# StairLights.net
KiCad netlist of a schematic drawn in EAGLE
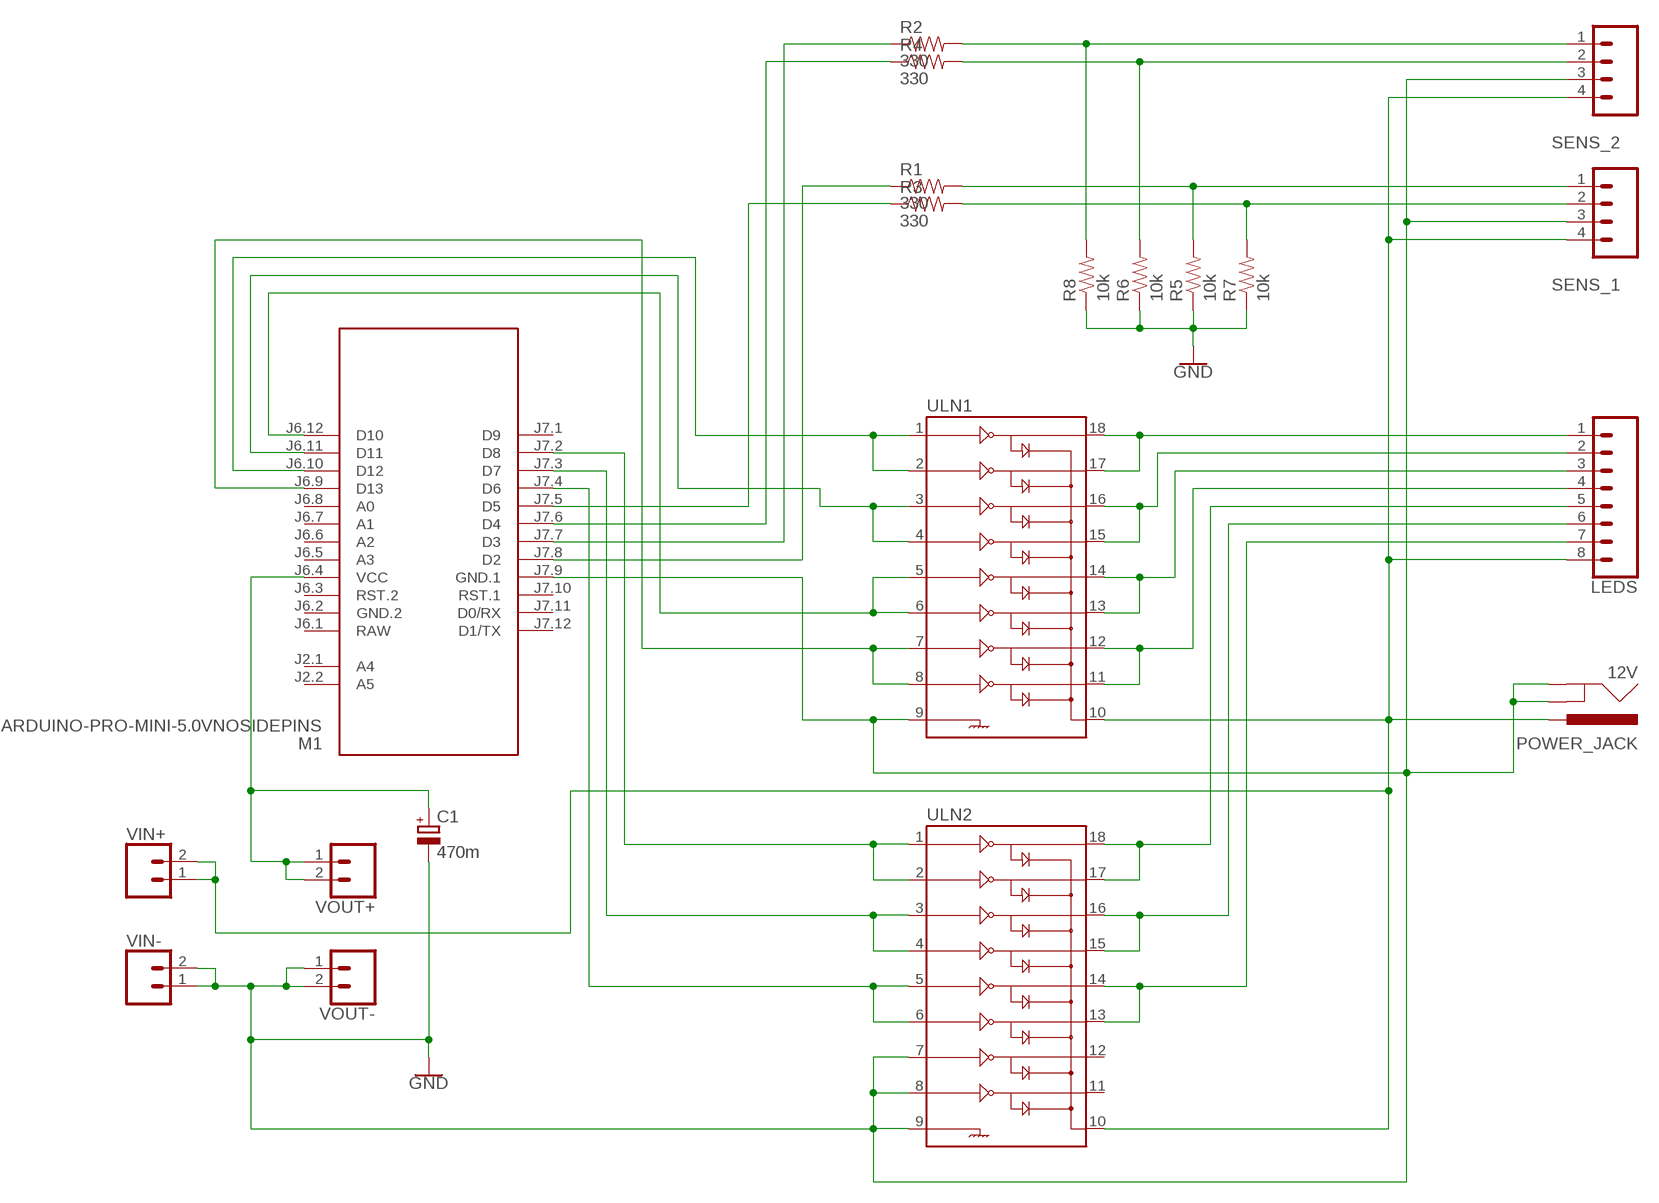
[diagram p0: schematic, sheet 1]

(export (version "E")
  (design (tool "Eeschema 10.0.6"))
  (components
    (comp (ref "12V")
      (value "POWER_JACK")
      (footprint "eagle-import:POWER_JACK_PTH")
      (libsource (lib "eagle-import") (part "POWER_JACK"))
    )
    (comp (ref "C1")
      (value "470m")
      (footprint "eagle-import:E5-5")
      (libsource (lib "eagle-import") (part "CPOL-EUE5-5"))
    )
    (comp (ref "LEDS")
      (value "CONN_08LONGPADS")
      (footprint "eagle-import:1X08_LONGPADS")
      (libsource (lib "eagle-import") (part "CONN_08LONGPADS"))
    )
    (comp (ref "M1")
      (value "ARDUINO-PRO-MINI-5.0VNOSIDEPINS")
      (footprint "eagle-import:ARDUINO-PRO-MINI")
      (libsource (lib "eagle-import") (part "ARDUINO-PRO-MINI-NOSIDEPINS5.0V"))
    )
    (comp (ref "R1")
      (value "330")
      (footprint "eagle-import:AXIAL-0.3")
      (libsource (lib "eagle-import") (part "330OHM-HORIZ-1/10W-5%"))
    )
    (comp (ref "R2")
      (value "330")
      (footprint "eagle-import:AXIAL-0.3")
      (libsource (lib "eagle-import") (part "330OHM-HORIZ-1/10W-5%"))
    )
    (comp (ref "R3")
      (value "330")
      (footprint "eagle-import:AXIAL-0.3")
      (libsource (lib "eagle-import") (part "330OHM-HORIZ-1/10W-5%"))
    )
    (comp (ref "R4")
      (value "330")
      (footprint "eagle-import:AXIAL-0.3")
      (libsource (lib "eagle-import") (part "330OHM-HORIZ-1/10W-5%"))
    )
    (comp (ref "R5")
      (value "10k")
      (footprint "eagle-import:AXIAL-0.3")
      (libsource (lib "eagle-import") (part "330OHM-HORIZ-1/10W-5%"))
    )
    (comp (ref "R6")
      (value "10k")
      (footprint "eagle-import:AXIAL-0.3")
      (libsource (lib "eagle-import") (part "330OHM-HORIZ-1/10W-5%"))
    )
    (comp (ref "R7")
      (value "10k")
      (footprint "eagle-import:AXIAL-0.3")
      (libsource (lib "eagle-import") (part "330OHM-HORIZ-1/10W-5%"))
    )
    (comp (ref "R8")
      (value "10k")
      (footprint "eagle-import:AXIAL-0.3")
      (libsource (lib "eagle-import") (part "330OHM-HORIZ-1/10W-5%"))
    )
    (comp (ref "SENS_1")
      (value "CONN_04LONGPADS")
      (footprint "eagle-import:1X04_LONGPADS")
      (libsource (lib "eagle-import") (part "CONN_04LONGPADS"))
    )
    (comp (ref "SENS_2")
      (value "CONN_04LONGPADS")
      (footprint "eagle-import:1X04_LONGPADS")
      (libsource (lib "eagle-import") (part "CONN_04LONGPADS"))
    )
    (comp (ref "ULN1")
      (value "ULN2803DIP")
      (footprint "eagle-import:DIL18")
      (libsource (lib "eagle-import") (part "ULN2803DIP"))
    )
    (comp (ref "ULN2")
      (value "ULN2803DIP")
      (footprint "eagle-import:DIL18")
      (libsource (lib "eagle-import") (part "ULN2803DIP"))
    )
    (comp (ref "VIN+")
      (value "CONN_02")
      (footprint "eagle-import:1X02")
      (libsource (lib "eagle-import") (part "CONN_02"))
    )
    (comp (ref "VIN-")
      (value "CONN_02")
      (footprint "eagle-import:1X02")
      (libsource (lib "eagle-import") (part "CONN_02"))
    )
    (comp (ref "VOUT+")
      (value "CONN_02")
      (footprint "eagle-import:1X02")
      (libsource (lib "eagle-import") (part "CONN_02"))
    )
    (comp (ref "VOUT-")
      (value "CONN_02")
      (footprint "eagle-import:1X02")
      (libsource (lib "eagle-import") (part "CONN_02"))
    )
  )
  (nets
    (net (code "1") (name "/GND.2") (class "Default")
      (node (ref "M1") (pin "J6.2") (pinfunction "GND.2_J6.2") (pintype "power_in"))
    )
    (net (code "2") (name "/RAW") (class "Default")
      (node (ref "M1") (pin "J6.1") (pinfunction "RAW_J6.1") (pintype "power_in"))
    )
    (net (code "3") (name "GND") (class "Default")
      (node (ref "12V") (pin "GND") (pinfunction "GND_GND") (pintype "bidirectional"))
      (node (ref "12V") (pin "GNDBREAK") (pinfunction "GNDBREAK_GNDBREAK") (pintype "bidirectional"))
      (node (ref "C1") (pin "-") (pinfunction "-_-") (pintype "passive"))
      (node (ref "M1") (pin "J7.9") (pinfunction "GND.1_J7.9") (pintype "power_in"))
      (node (ref "R5") (pin "P$1") (pinfunction "1_P$1") (pintype "passive"))
      (node (ref "R6") (pin "P$1") (pinfunction "1_P$1") (pintype "passive"))
      (node (ref "R7") (pin "P$1") (pinfunction "1_P$1") (pintype "passive"))
      (node (ref "R8") (pin "P$1") (pinfunction "1_P$1") (pintype "passive"))
      (node (ref "SENS_1") (pin "3") (pinfunction "3_3") (pintype "passive"))
      (node (ref "SENS_2") (pin "3") (pinfunction "3_3") (pintype "passive"))
      (node (ref "ULN1") (pin "9") (pinfunction "9_9") (pintype "bidirectional"))
      (node (ref "ULN2") (pin "7") (pinfunction "7_7") (pintype "bidirectional"))
      (node (ref "ULN2") (pin "8") (pinfunction "8_8") (pintype "bidirectional"))
      (node (ref "ULN2") (pin "9") (pinfunction "9_9") (pintype "bidirectional"))
      (node (ref "VIN-") (pin "1") (pinfunction "1_1") (pintype "passive"))
      (node (ref "VIN-") (pin "2") (pinfunction "2_2") (pintype "passive"))
      (node (ref "VOUT-") (pin "1") (pinfunction "1_1") (pintype "passive"))
      (node (ref "VOUT-") (pin "2") (pinfunction "2_2") (pintype "passive"))
    )
    (net (code "4") (name "Net-(12V-PadPWR)") (class "Default")
      (node (ref "12V") (pin "PWR") (pinfunction "PWR_PWR") (pintype "bidirectional"))
      (node (ref "LEDS") (pin "8") (pinfunction "8_8") (pintype "passive"))
      (node (ref "SENS_1") (pin "4") (pinfunction "4_4") (pintype "passive"))
      (node (ref "SENS_2") (pin "4") (pinfunction "4_4") (pintype "passive"))
      (node (ref "ULN1") (pin "10") (pinfunction "10_10") (pintype "bidirectional"))
      (node (ref "ULN2") (pin "10") (pinfunction "10_10") (pintype "bidirectional"))
      (node (ref "VIN+") (pin "1") (pinfunction "1_1") (pintype "passive"))
      (node (ref "VIN+") (pin "2") (pinfunction "2_2") (pintype "passive"))
    )
    (net (code "5") (name "Net-(LEDS-Pad1)") (class "Default")
      (node (ref "LEDS") (pin "1") (pinfunction "1_1") (pintype "passive"))
      (node (ref "ULN1") (pin "17") (pinfunction "17_17") (pintype "bidirectional"))
      (node (ref "ULN1") (pin "18") (pinfunction "18_18") (pintype "bidirectional"))
    )
    (net (code "6") (name "Net-(LEDS-Pad2)") (class "Default")
      (node (ref "LEDS") (pin "2") (pinfunction "2_2") (pintype "passive"))
      (node (ref "ULN1") (pin "15") (pinfunction "15_15") (pintype "bidirectional"))
      (node (ref "ULN1") (pin "16") (pinfunction "16_16") (pintype "bidirectional"))
    )
    (net (code "7") (name "Net-(LEDS-Pad3)") (class "Default")
      (node (ref "LEDS") (pin "3") (pinfunction "3_3") (pintype "passive"))
      (node (ref "ULN1") (pin "13") (pinfunction "13_13") (pintype "bidirectional"))
      (node (ref "ULN1") (pin "14") (pinfunction "14_14") (pintype "bidirectional"))
    )
    (net (code "8") (name "Net-(LEDS-Pad4)") (class "Default")
      (node (ref "LEDS") (pin "4") (pinfunction "4_4") (pintype "passive"))
      (node (ref "ULN1") (pin "11") (pinfunction "11_11") (pintype "bidirectional"))
      (node (ref "ULN1") (pin "12") (pinfunction "12_12") (pintype "bidirectional"))
    )
    (net (code "9") (name "Net-(LEDS-Pad5)") (class "Default")
      (node (ref "LEDS") (pin "5") (pinfunction "5_5") (pintype "passive"))
      (node (ref "ULN2") (pin "17") (pinfunction "17_17") (pintype "bidirectional"))
      (node (ref "ULN2") (pin "18") (pinfunction "18_18") (pintype "bidirectional"))
    )
    (net (code "10") (name "Net-(LEDS-Pad6)") (class "Default")
      (node (ref "LEDS") (pin "6") (pinfunction "6_6") (pintype "passive"))
      (node (ref "ULN2") (pin "15") (pinfunction "15_15") (pintype "bidirectional"))
      (node (ref "ULN2") (pin "16") (pinfunction "16_16") (pintype "bidirectional"))
    )
    (net (code "11") (name "Net-(LEDS-Pad7)") (class "Default")
      (node (ref "LEDS") (pin "7") (pinfunction "7_7") (pintype "passive"))
      (node (ref "ULN2") (pin "13") (pinfunction "13_13") (pintype "bidirectional"))
      (node (ref "ULN2") (pin "14") (pinfunction "14_14") (pintype "bidirectional"))
    )
    (net (code "12") (name "Net-(M1-D2)") (class "Default")
      (node (ref "M1") (pin "J7.8") (pinfunction "D2_J7.8") (pintype "bidirectional"))
      (node (ref "R1") (pin "P$1") (pinfunction "1_P$1") (pintype "passive"))
    )
    (net (code "13") (name "Net-(M1-D3)") (class "Default")
      (node (ref "M1") (pin "J7.7") (pinfunction "D3_J7.7") (pintype "bidirectional"))
      (node (ref "R2") (pin "P$1") (pinfunction "1_P$1") (pintype "passive"))
    )
    (net (code "14") (name "Net-(M1-D4)") (class "Default")
      (node (ref "M1") (pin "J7.6") (pinfunction "D4_J7.6") (pintype "bidirectional"))
      (node (ref "R4") (pin "P$1") (pinfunction "1_P$1") (pintype "passive"))
    )
    (net (code "15") (name "Net-(M1-D5)") (class "Default")
      (node (ref "M1") (pin "J7.5") (pinfunction "D5_J7.5") (pintype "bidirectional"))
      (node (ref "R3") (pin "P$1") (pinfunction "1_P$1") (pintype "passive"))
    )
    (net (code "16") (name "Net-(M1-D6)") (class "Default")
      (node (ref "M1") (pin "J7.4") (pinfunction "D6_J7.4") (pintype "bidirectional"))
      (node (ref "ULN2") (pin "5") (pinfunction "5_5") (pintype "bidirectional"))
      (node (ref "ULN2") (pin "6") (pinfunction "6_6") (pintype "bidirectional"))
    )
    (net (code "17") (name "Net-(M1-D7)") (class "Default")
      (node (ref "M1") (pin "J7.3") (pinfunction "D7_J7.3") (pintype "bidirectional"))
      (node (ref "ULN2") (pin "3") (pinfunction "3_3") (pintype "bidirectional"))
      (node (ref "ULN2") (pin "4") (pinfunction "4_4") (pintype "bidirectional"))
    )
    (net (code "18") (name "Net-(M1-D8)") (class "Default")
      (node (ref "M1") (pin "J7.2") (pinfunction "D8_J7.2") (pintype "bidirectional"))
      (node (ref "ULN2") (pin "1") (pinfunction "1_1") (pintype "bidirectional"))
      (node (ref "ULN2") (pin "2") (pinfunction "2_2") (pintype "bidirectional"))
    )
    (net (code "19") (name "Net-(M1-D10)") (class "Default")
      (node (ref "M1") (pin "J6.12") (pinfunction "D10_J6.12") (pintype "bidirectional"))
      (node (ref "ULN1") (pin "5") (pinfunction "5_5") (pintype "bidirectional"))
      (node (ref "ULN1") (pin "6") (pinfunction "6_6") (pintype "bidirectional"))
    )
    (net (code "20") (name "Net-(M1-D11)") (class "Default")
      (node (ref "M1") (pin "J6.11") (pinfunction "D11_J6.11") (pintype "bidirectional"))
      (node (ref "ULN1") (pin "3") (pinfunction "3_3") (pintype "bidirectional"))
      (node (ref "ULN1") (pin "4") (pinfunction "4_4") (pintype "bidirectional"))
    )
    (net (code "21") (name "Net-(M1-D12)") (class "Default")
      (node (ref "M1") (pin "J6.10") (pinfunction "D12_J6.10") (pintype "bidirectional"))
      (node (ref "ULN1") (pin "1") (pinfunction "1_1") (pintype "bidirectional"))
      (node (ref "ULN1") (pin "2") (pinfunction "2_2") (pintype "bidirectional"))
    )
    (net (code "22") (name "Net-(M1-D13)") (class "Default")
      (node (ref "M1") (pin "J6.9") (pinfunction "D13_J6.9") (pintype "bidirectional"))
      (node (ref "ULN1") (pin "7") (pinfunction "7_7") (pintype "bidirectional"))
      (node (ref "ULN1") (pin "8") (pinfunction "8_8") (pintype "bidirectional"))
    )
    (net (code "23") (name "Net-(M1-VCC)") (class "Default")
      (node (ref "C1") (pin "+") (pinfunction "+_+") (pintype "passive"))
      (node (ref "M1") (pin "J6.4") (pinfunction "VCC_J6.4") (pintype "power_in"))
      (node (ref "VOUT+") (pin "1") (pinfunction "1_1") (pintype "passive"))
      (node (ref "VOUT+") (pin "2") (pinfunction "2_2") (pintype "passive"))
    )
    (net (code "24") (name "Net-(R1-2)") (class "Default")
      (node (ref "R1") (pin "P$2") (pinfunction "2_P$2") (pintype "passive"))
      (node (ref "R5") (pin "P$2") (pinfunction "2_P$2") (pintype "passive"))
      (node (ref "SENS_1") (pin "1") (pinfunction "1_1") (pintype "passive"))
    )
    (net (code "25") (name "Net-(R2-2)") (class "Default")
      (node (ref "R2") (pin "P$2") (pinfunction "2_P$2") (pintype "passive"))
      (node (ref "R8") (pin "P$2") (pinfunction "2_P$2") (pintype "passive"))
      (node (ref "SENS_2") (pin "1") (pinfunction "1_1") (pintype "passive"))
    )
    (net (code "26") (name "Net-(R3-2)") (class "Default")
      (node (ref "R3") (pin "P$2") (pinfunction "2_P$2") (pintype "passive"))
      (node (ref "R7") (pin "P$2") (pinfunction "2_P$2") (pintype "passive"))
      (node (ref "SENS_1") (pin "2") (pinfunction "2_2") (pintype "passive"))
    )
    (net (code "27") (name "Net-(R4-2)") (class "Default")
      (node (ref "R4") (pin "P$2") (pinfunction "2_P$2") (pintype "passive"))
      (node (ref "R6") (pin "P$2") (pinfunction "2_P$2") (pintype "passive"))
      (node (ref "SENS_2") (pin "2") (pinfunction "2_2") (pintype "passive"))
    )
    (net (code "28") (name "unconnected-(M1-A0-PadJ6.8)") (class "Default")
      (node (ref "M1") (pin "J6.8") (pinfunction "A0_J6.8") (pintype "bidirectional"))
    )
    (net (code "29") (name "unconnected-(M1-A1-PadJ6.7)") (class "Default")
      (node (ref "M1") (pin "J6.7") (pinfunction "A1_J6.7") (pintype "bidirectional"))
    )
    (net (code "30") (name "unconnected-(M1-A2-PadJ6.6)") (class "Default")
      (node (ref "M1") (pin "J6.6") (pinfunction "A2_J6.6") (pintype "bidirectional"))
    )
    (net (code "31") (name "unconnected-(M1-A3-PadJ6.5)") (class "Default")
      (node (ref "M1") (pin "J6.5") (pinfunction "A3_J6.5") (pintype "bidirectional"))
    )
    (net (code "32") (name "unconnected-(M1-A4-PadJ2.1)") (class "Default")
      (node (ref "M1") (pin "J2.1") (pinfunction "A4_J2.1") (pintype "bidirectional"))
    )
    (net (code "33") (name "unconnected-(M1-A5-PadJ2.2)") (class "Default")
      (node (ref "M1") (pin "J2.2") (pinfunction "A5_J2.2") (pintype "bidirectional"))
    )
    (net (code "34") (name "unconnected-(M1-D0{slash}RX-PadJ7.11)") (class "Default")
      (node (ref "M1") (pin "J7.11") (pinfunction "D0/RX_J7.11") (pintype "bidirectional"))
    )
    (net (code "35") (name "unconnected-(M1-D1{slash}TX-PadJ7.12)") (class "Default")
      (node (ref "M1") (pin "J7.12") (pinfunction "D1/TX_J7.12") (pintype "bidirectional"))
    )
    (net (code "36") (name "unconnected-(M1-D9-PadJ7.1)") (class "Default")
      (node (ref "M1") (pin "J7.1") (pinfunction "D9_J7.1") (pintype "bidirectional"))
    )
    (net (code "37") (name "unconnected-(M1-RST.1-PadJ7.10)") (class "Default")
      (node (ref "M1") (pin "J7.10") (pinfunction "RST.1_J7.10") (pintype "bidirectional"))
    )
    (net (code "38") (name "unconnected-(M1-RST.2-PadJ6.3)") (class "Default")
      (node (ref "M1") (pin "J6.3") (pinfunction "RST.2_J6.3") (pintype "bidirectional"))
    )
    (net (code "39") (name "unconnected-(ULN2-Pad11)") (class "Default")
      (node (ref "ULN2") (pin "11") (pinfunction "11_11") (pintype "bidirectional"))
    )
    (net (code "40") (name "unconnected-(ULN2-Pad12)") (class "Default")
      (node (ref "ULN2") (pin "12") (pinfunction "12_12") (pintype "bidirectional"))
    )
  )
)
